# Board_4_Buttons_WS-TATV.net
KiCad netlist of a schematic drawn in EAGLE
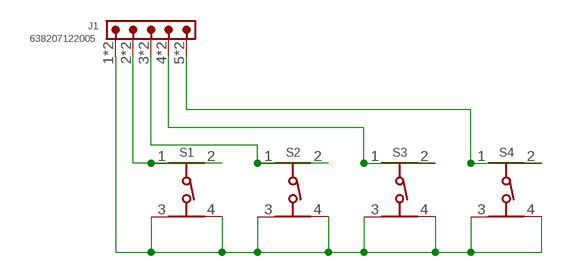
[diagram p0: schematic, sheet 1]

(export (version "E")
  (design (tool "Eeschema 10.0.6"))
  (components
    (comp (ref "J1")
      (value "638207122005")
      (footprint "eagle-import:638207122005")
      (libsource (lib "eagle-import") (part "638207122005"))
    )
    (comp (ref "S1")
      (value "430456073736")
      (footprint "eagle-import:4304X60737X6")
      (libsource (lib "eagle-import") (part "430456073736"))
    )
    (comp (ref "S2")
      (value "430456073736")
      (footprint "eagle-import:4304X60737X6")
      (libsource (lib "eagle-import") (part "430456073736"))
    )
    (comp (ref "S3")
      (value "430456073736")
      (footprint "eagle-import:4304X60737X6")
      (libsource (lib "eagle-import") (part "430456073736"))
    )
    (comp (ref "S4")
      (value "430456073736")
      (footprint "eagle-import:4304X60737X6")
      (libsource (lib "eagle-import") (part "430456073736"))
    )
  )
  (nets
    (net (code "1") (name "Net-(S1-2)") (class "Default")
      (node (ref "J1") (pin "1") (pinfunction "1_1") (pintype "passive"))
      (node (ref "J1") (pin "A1") (pinfunction "1_A1") (pintype "passive"))
      (node (ref "S1") (pin "3") (pinfunction "2_3") (pintype "passive"))
      (node (ref "S1") (pin "4") (pinfunction "4_4") (pintype "passive"))
      (node (ref "S2") (pin "3") (pinfunction "2_3") (pintype "passive"))
      (node (ref "S2") (pin "4") (pinfunction "4_4") (pintype "passive"))
      (node (ref "S3") (pin "3") (pinfunction "2_3") (pintype "passive"))
      (node (ref "S3") (pin "4") (pinfunction "4_4") (pintype "passive"))
      (node (ref "S4") (pin "3") (pinfunction "2_3") (pintype "passive"))
      (node (ref "S4") (pin "4") (pinfunction "4_4") (pintype "passive"))
    )
    (net (code "2") (name "Net-(S1-3)") (class "Default")
      (node (ref "J1") (pin "2") (pinfunction "2_2") (pintype "passive"))
      (node (ref "J1") (pin "A2") (pinfunction "2_A2") (pintype "passive"))
      (node (ref "S1") (pin "1") (pinfunction "1_1") (pintype "passive"))
      (node (ref "S1") (pin "2") (pinfunction "3_2") (pintype "passive"))
    )
    (net (code "3") (name "Net-(S2-3)") (class "Default")
      (node (ref "J1") (pin "3") (pinfunction "3_3") (pintype "passive"))
      (node (ref "J1") (pin "A3") (pinfunction "3_A3") (pintype "passive"))
      (node (ref "S2") (pin "1") (pinfunction "1_1") (pintype "passive"))
      (node (ref "S2") (pin "2") (pinfunction "3_2") (pintype "passive"))
    )
    (net (code "4") (name "Net-(S3-3)") (class "Default")
      (node (ref "J1") (pin "4") (pinfunction "4_4") (pintype "passive"))
      (node (ref "J1") (pin "A4") (pinfunction "4_A4") (pintype "passive"))
      (node (ref "S3") (pin "1") (pinfunction "1_1") (pintype "passive"))
      (node (ref "S3") (pin "2") (pinfunction "3_2") (pintype "passive"))
    )
    (net (code "5") (name "Net-(S4-3)") (class "Default")
      (node (ref "J1") (pin "5") (pinfunction "5_5") (pintype "passive"))
      (node (ref "J1") (pin "A5") (pinfunction "5_A5") (pintype "passive"))
      (node (ref "S4") (pin "1") (pinfunction "1_1") (pintype "passive"))
      (node (ref "S4") (pin "2") (pinfunction "3_2") (pintype "passive"))
    )
  )
)
